# ACS770_breakout_v0_2.net
KiCad netlist of a schematic drawn in EAGLE
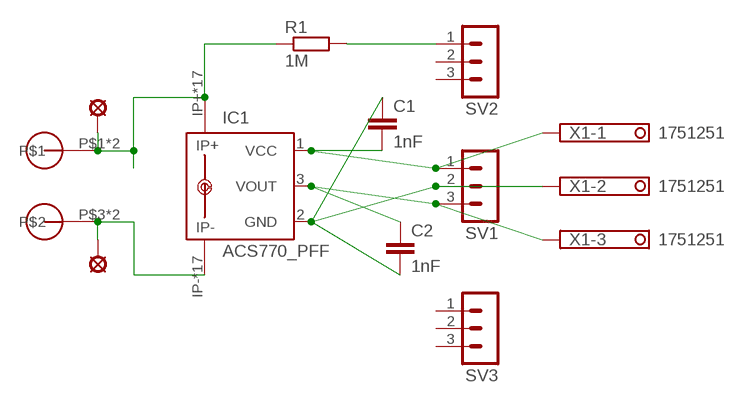
[diagram p0: schematic, sheet 1]

(export (version "E")
  (design (tool "Eeschema 10.0.6"))
  (components
    (comp (ref "C1")
      (value "1nF")
      (footprint "eagle-import:C025-025X050")
      (libsource (lib "eagle-import") (part "C-EU025-025X050"))
    )
    (comp (ref "C2")
      (value "1nF")
      (footprint "eagle-import:C025-025X050")
      (libsource (lib "eagle-import") (part "C-EU025-025X050"))
    )
    (comp (ref "IC1")
      (value "ACS770_PFF")
      (footprint "eagle-import:CB-PFF")
      (fields (field (name "MPN") "ACS758LCB-050B-PFF-T"))
      (libsource (lib "eagle-import") (part "ACS758LCB-050B-PFF-T"))
    )
    (comp (ref "LSP1")
      (value "LSP13")
      (footprint "eagle-import:LSP13")
      (libsource (lib "eagle-import") (part "LSP13"))
    )
    (comp (ref "LSP2")
      (value "LSP13")
      (footprint "eagle-import:LSP13")
      (libsource (lib "eagle-import") (part "LSP13"))
    )
    (comp (ref "R1")
      (value "1M")
      (footprint "eagle-import:0411_15")
      (libsource (lib "eagle-import") (part "R-EU_0411/15"))
    )
    (comp (ref "SV1")
      (value "MA03-1")
      (footprint "eagle-import:MA03-1")
      (libsource (lib "eagle-import") (part "MA03-1"))
    )
    (comp (ref "SV2")
      (value "MA03-1")
      (footprint "eagle-import:MA03-1")
      (libsource (lib "eagle-import") (part "MA03-1"))
    )
    (comp (ref "SV3")
      (value "MA03-1")
      (footprint "eagle-import:MA03-1")
      (libsource (lib "eagle-import") (part "MA03-1"))
    )
    (comp (ref "U$5")
      (value "MOLEX_39970-003")
      (footprint "eagle-import:2_10,16")
      (libsource (lib "eagle-import") (part "MOLEX_39970-003"))
    )
    (comp (ref "X1")
      (value "1751251")
      (footprint "eagle-import:1751251")
      (libsource (lib "eagle-import") (part "1751251"))
    )
  )
  (nets
    (net (code "1") (name "Net-(IC1-GND)") (class "Default")
      (node (ref "C1") (pin "1") (pinfunction "1_1") (pintype "passive"))
      (node (ref "C2") (pin "2") (pinfunction "2_2") (pintype "passive"))
      (node (ref "IC1") (pin "2") (pinfunction "GND_2") (pintype "power_in"))
      (node (ref "SV1") (pin "2") (pinfunction "2_2") (pintype "passive"))
      (node (ref "X1") (pin "2") (pinfunction "K_2") (pintype "passive"))
    )
    (net (code "2") (name "Net-(IC1-IP+-PadIP+@10)") (class "Default")
      (node (ref "IC1") (pin "IP+") (pinfunction "IP+_IP+") (pintype "passive"))
      (node (ref "IC1") (pin "IP+@10") (pinfunction "IP+_IP+@10") (pintype "passive"))
      (node (ref "IC1") (pin "IP+@11") (pinfunction "IP+_IP+@11") (pintype "passive"))
      (node (ref "IC1") (pin "IP+@12") (pinfunction "IP+_IP+@12") (pintype "passive"))
      (node (ref "IC1") (pin "IP+@13") (pinfunction "IP+_IP+@13") (pintype "passive"))
      (node (ref "IC1") (pin "IP+@14") (pinfunction "IP+_IP+@14") (pintype "passive"))
      (node (ref "IC1") (pin "IP+@15") (pinfunction "IP+_IP+@15") (pintype "passive"))
      (node (ref "IC1") (pin "IP+@16") (pinfunction "IP+_IP+@16") (pintype "passive"))
      (node (ref "IC1") (pin "IP+@17") (pinfunction "IP+_IP+@17") (pintype "passive"))
      (node (ref "IC1") (pin "IP+@2") (pinfunction "IP+_IP+@2") (pintype "passive"))
      (node (ref "IC1") (pin "IP+@3") (pinfunction "IP+_IP+@3") (pintype "passive"))
      (node (ref "IC1") (pin "IP+@4") (pinfunction "IP+_IP+@4") (pintype "passive"))
      (node (ref "IC1") (pin "IP+@5") (pinfunction "IP+_IP+@5") (pintype "passive"))
      (node (ref "IC1") (pin "IP+@6") (pinfunction "IP+_IP+@6") (pintype "passive"))
      (node (ref "IC1") (pin "IP+@7") (pinfunction "IP+_IP+@7") (pintype "passive"))
      (node (ref "IC1") (pin "IP+@8") (pinfunction "IP+_IP+@8") (pintype "passive"))
      (node (ref "IC1") (pin "IP+@9") (pinfunction "IP+_IP+@9") (pintype "passive"))
      (node (ref "LSP1") (pin "MP") (pinfunction "MP_MP") (pintype "passive"))
      (node (ref "R1") (pin "1") (pinfunction "1_1") (pintype "passive"))
      (node (ref "U$5") (pin "P$1") (pinfunction "P$1_P$1") (pintype "power_in"))
      (node (ref "U$5") (pin "P$2") (pinfunction "P$1_P$2") (pintype "power_in"))
    )
    (net (code "3") (name "Net-(IC1-IP--PadIP-@10)") (class "Default")
      (node (ref "IC1") (pin "IP-") (pinfunction "IP-_IP-") (pintype "passive"))
      (node (ref "IC1") (pin "IP-@10") (pinfunction "IP-_IP-@10") (pintype "passive"))
      (node (ref "IC1") (pin "IP-@11") (pinfunction "IP-_IP-@11") (pintype "passive"))
      (node (ref "IC1") (pin "IP-@12") (pinfunction "IP-_IP-@12") (pintype "passive"))
      (node (ref "IC1") (pin "IP-@13") (pinfunction "IP-_IP-@13") (pintype "passive"))
      (node (ref "IC1") (pin "IP-@14") (pinfunction "IP-_IP-@14") (pintype "passive"))
      (node (ref "IC1") (pin "IP-@15") (pinfunction "IP-_IP-@15") (pintype "passive"))
      (node (ref "IC1") (pin "IP-@16") (pinfunction "IP-_IP-@16") (pintype "passive"))
      (node (ref "IC1") (pin "IP-@17") (pinfunction "IP-_IP-@17") (pintype "passive"))
      (node (ref "IC1") (pin "IP-@2") (pinfunction "IP-_IP-@2") (pintype "passive"))
      (node (ref "IC1") (pin "IP-@3") (pinfunction "IP-_IP-@3") (pintype "passive"))
      (node (ref "IC1") (pin "IP-@4") (pinfunction "IP-_IP-@4") (pintype "passive"))
      (node (ref "IC1") (pin "IP-@5") (pinfunction "IP-_IP-@5") (pintype "passive"))
      (node (ref "IC1") (pin "IP-@6") (pinfunction "IP-_IP-@6") (pintype "passive"))
      (node (ref "IC1") (pin "IP-@7") (pinfunction "IP-_IP-@7") (pintype "passive"))
      (node (ref "IC1") (pin "IP-@8") (pinfunction "IP-_IP-@8") (pintype "passive"))
      (node (ref "IC1") (pin "IP-@9") (pinfunction "IP-_IP-@9") (pintype "passive"))
      (node (ref "LSP2") (pin "MP") (pinfunction "MP_MP") (pintype "passive"))
      (node (ref "U$5") (pin "P$3") (pinfunction "P$2_P$3") (pintype "power_in"))
      (node (ref "U$5") (pin "P$4") (pinfunction "P$2_P$4") (pintype "power_in"))
    )
    (net (code "4") (name "Net-(IC1-VCC)") (class "Default")
      (node (ref "C1") (pin "2") (pinfunction "2_2") (pintype "passive"))
      (node (ref "IC1") (pin "1") (pinfunction "VCC_1") (pintype "power_in"))
      (node (ref "SV1") (pin "1") (pinfunction "1_1") (pintype "passive"))
      (node (ref "X1") (pin "1") (pinfunction "K_1") (pintype "passive"))
    )
    (net (code "5") (name "Net-(IC1-VOUT)") (class "Default")
      (node (ref "C2") (pin "1") (pinfunction "1_1") (pintype "passive"))
      (node (ref "IC1") (pin "3") (pinfunction "VOUT_3") (pintype "output"))
      (node (ref "SV1") (pin "3") (pinfunction "3_3") (pintype "passive"))
      (node (ref "X1") (pin "3") (pinfunction "K_3") (pintype "passive"))
    )
    (net (code "6") (name "Net-(R1-Pad2)") (class "Default")
      (node (ref "R1") (pin "2") (pinfunction "2_2") (pintype "passive"))
      (node (ref "SV2") (pin "1") (pinfunction "1_1") (pintype "passive"))
    )
    (net (code "7") (name "unconnected-(SV2-Pad2)") (class "Default")
      (node (ref "SV2") (pin "2") (pinfunction "2_2") (pintype "passive"))
    )
    (net (code "8") (name "unconnected-(SV2-Pad3)") (class "Default")
      (node (ref "SV2") (pin "3") (pinfunction "3_3") (pintype "passive"))
    )
    (net (code "9") (name "unconnected-(SV3-Pad1)") (class "Default")
      (node (ref "SV3") (pin "1") (pinfunction "1_1") (pintype "passive"))
    )
    (net (code "10") (name "unconnected-(SV3-Pad2)") (class "Default")
      (node (ref "SV3") (pin "2") (pinfunction "2_2") (pintype "passive"))
    )
    (net (code "11") (name "unconnected-(SV3-Pad3)") (class "Default")
      (node (ref "SV3") (pin "3") (pinfunction "3_3") (pintype "passive"))
    )
  )
)
